# evpr.net
KiCad netlist of a schematic drawn in EAGLE
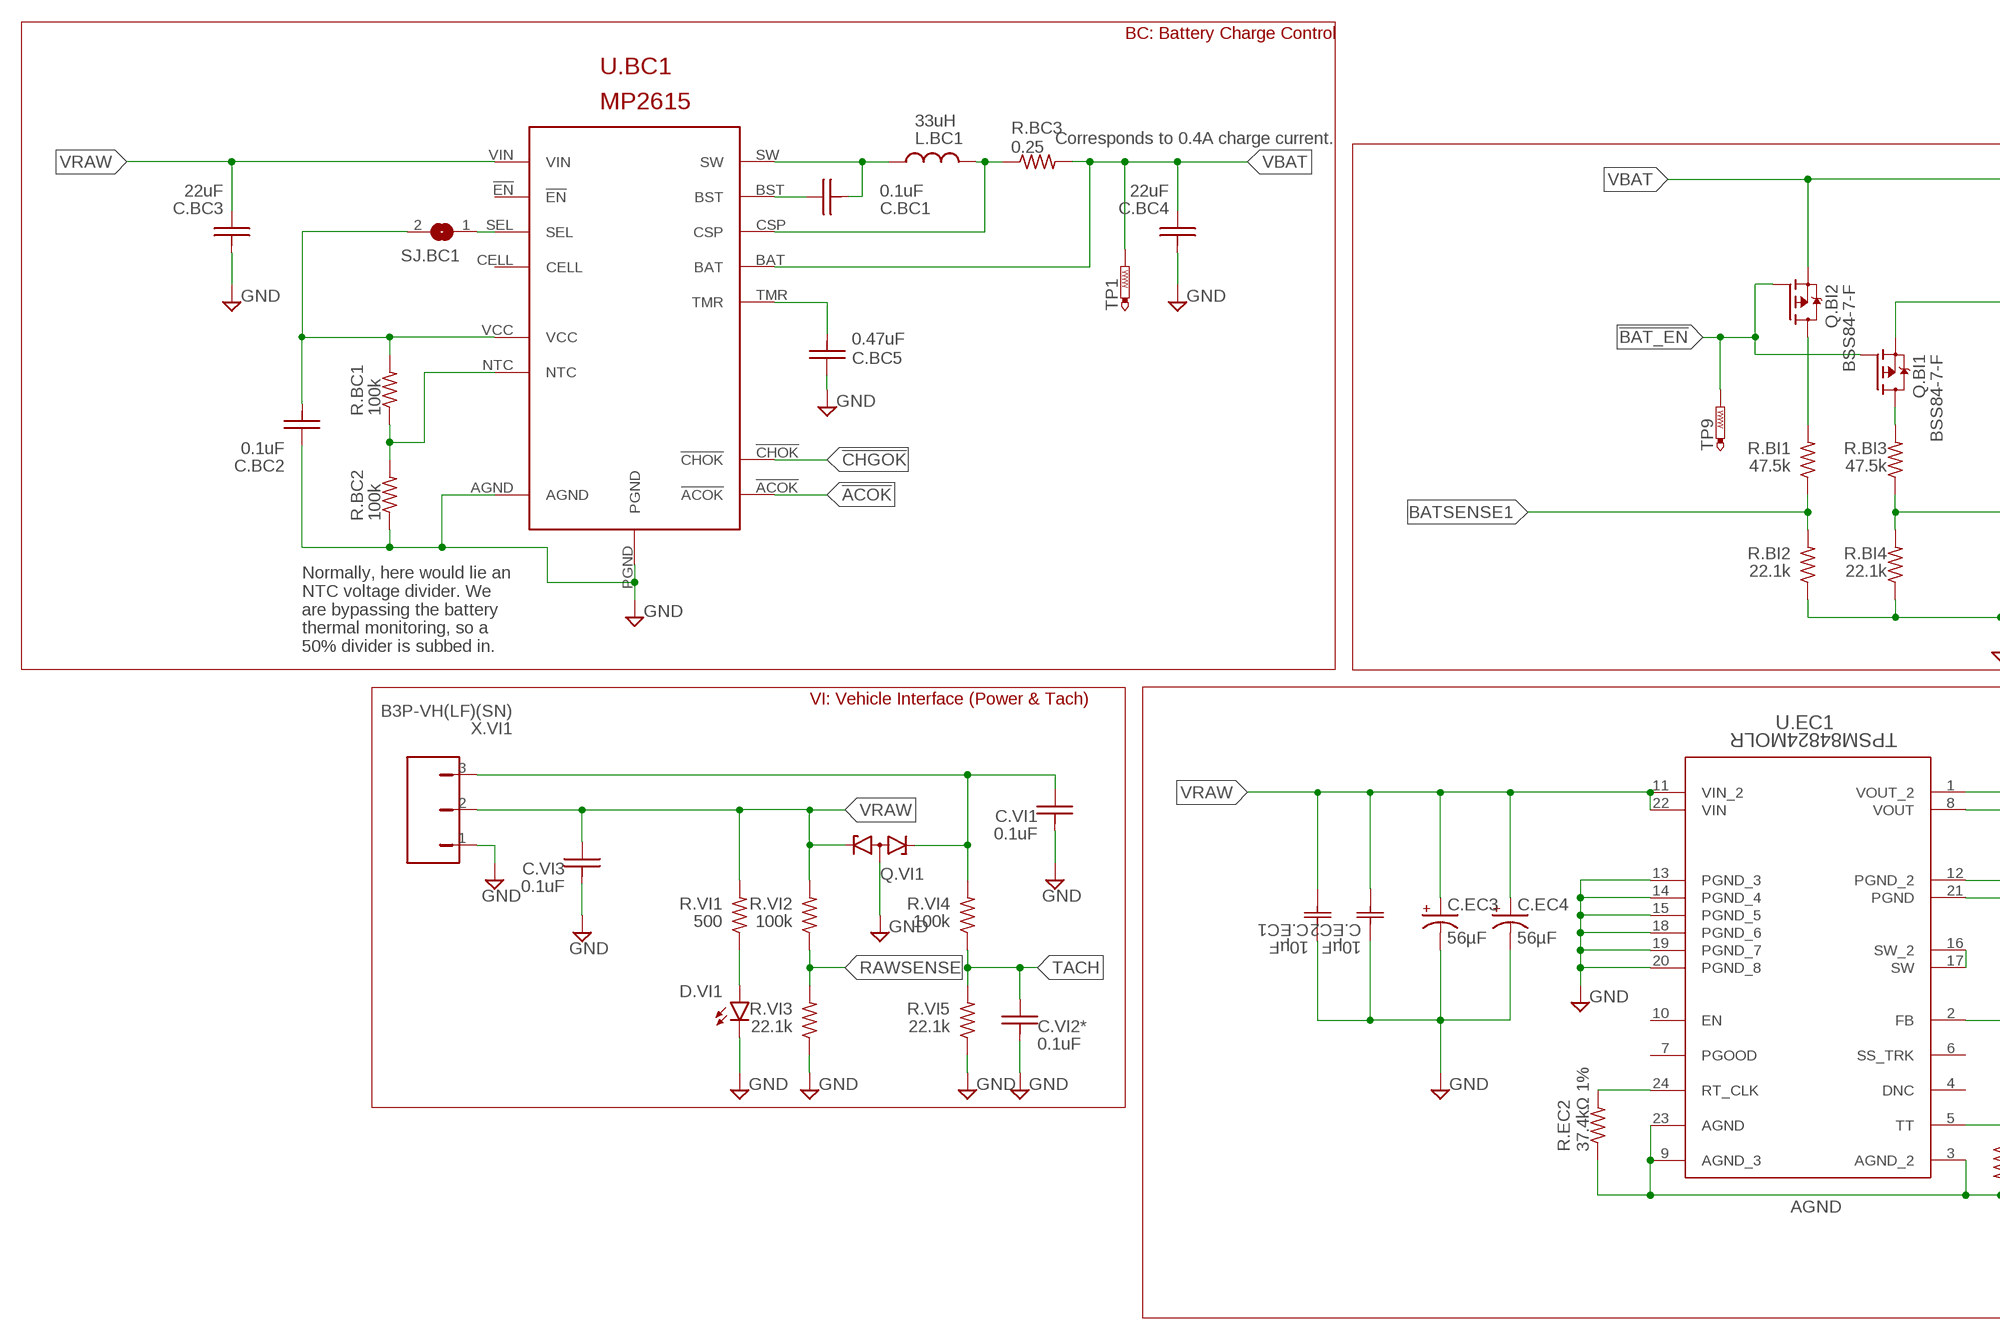
[diagram p0: schematic, sheet 1, part 1 of 2]
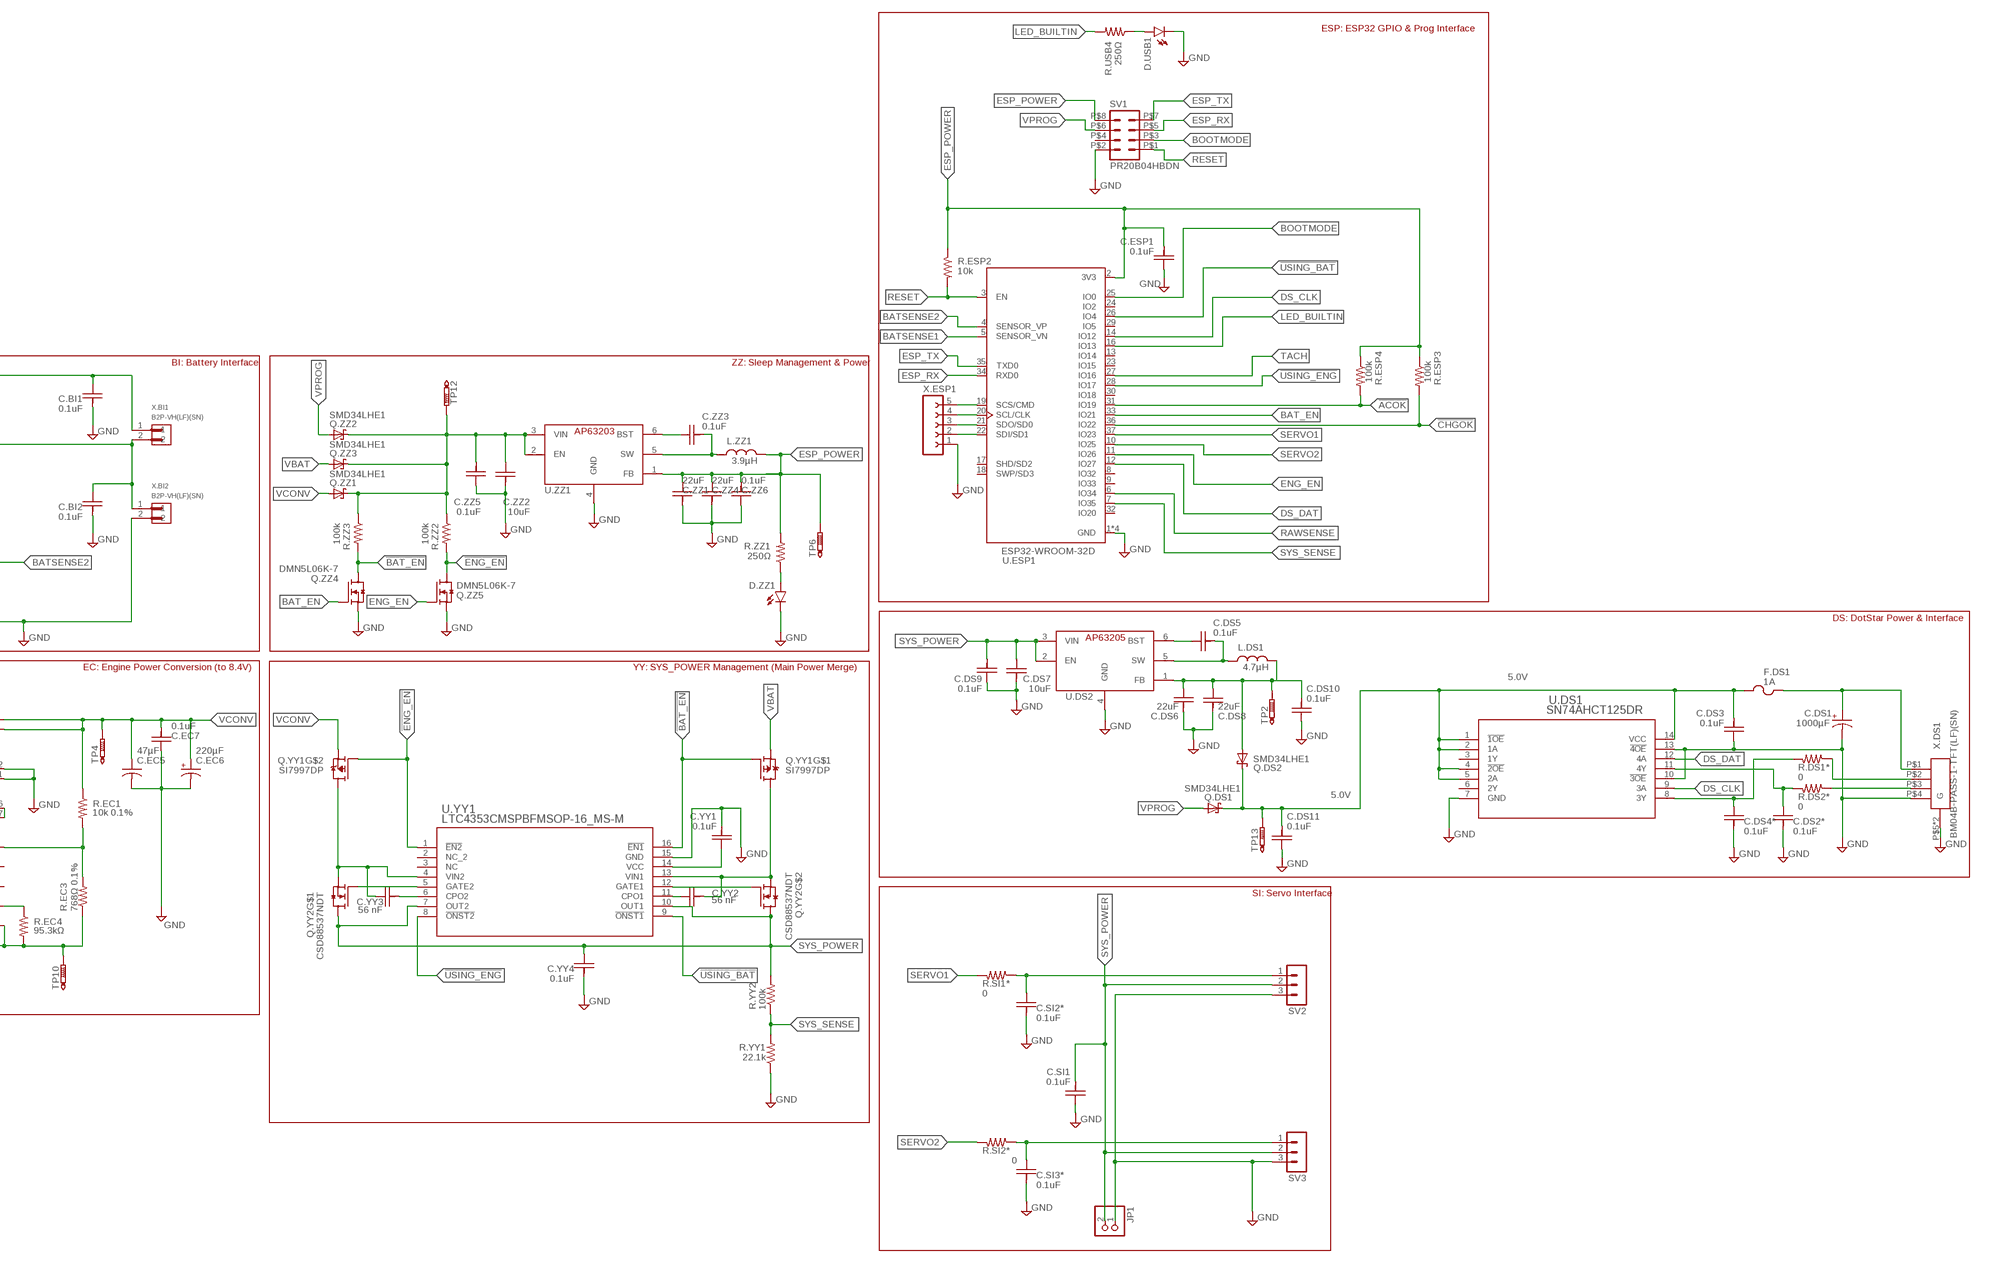
[diagram p1: schematic, sheet 1, part 2 of 2]

(export (version "E")
  (design (tool "Eeschema 10.0.6"))
  (components
    (comp (ref "C.BC1")
      (value "0.1uF")
      (footprint "eagle-import:C0603")
      (libsource (lib "eagle-import") (part "C0603"))
    )
    (comp (ref "C.BC2")
      (value "0.1uF")
      (footprint "eagle-import:C0603")
      (libsource (lib "eagle-import") (part "C0603"))
    )
    (comp (ref "C.BC3")
      (value "22uF")
      (footprint "eagle-import:C0603")
      (libsource (lib "eagle-import") (part "C0603"))
    )
    (comp (ref "C.BC4")
      (value "22uF")
      (footprint "eagle-import:C0603")
      (libsource (lib "eagle-import") (part "C0603"))
    )
    (comp (ref "C.BC5")
      (value "0.47uF")
      (footprint "eagle-import:C0603")
      (libsource (lib "eagle-import") (part "C0603"))
    )
    (comp (ref "C.BI1")
      (value "0.1uF")
      (footprint "eagle-import:C0603")
      (libsource (lib "eagle-import") (part "C0603"))
    )
    (comp (ref "C.BI2")
      (value "0.1uF")
      (footprint "eagle-import:C0603")
      (libsource (lib "eagle-import") (part "C0603"))
    )
    (comp (ref "C.DS1")
      (value "1000µF")
      (footprint "eagle-import:810RADCAN")
      (libsource (lib "eagle-import") (part "810RADCAP"))
    )
    (comp (ref "C.DS2*")
      (value "0.1uF")
      (footprint "eagle-import:C0603")
      (libsource (lib "eagle-import") (part "C0603"))
    )
    (comp (ref "C.DS3")
      (value "0.1uF")
      (footprint "eagle-import:C0603")
      (libsource (lib "eagle-import") (part "C0603"))
    )
    (comp (ref "C.DS4*")
      (value "0.1uF")
      (footprint "eagle-import:C0603")
      (libsource (lib "eagle-import") (part "C0603"))
    )
    (comp (ref "C.DS5")
      (value "0.1uF")
      (footprint "eagle-import:C0603")
      (libsource (lib "eagle-import") (part "C0603"))
    )
    (comp (ref "C.DS6")
      (value "22uF")
      (footprint "eagle-import:C0603")
      (libsource (lib "eagle-import") (part "C0603"))
    )
    (comp (ref "C.DS7")
      (value "10uF")
      (footprint "eagle-import:C0603")
      (libsource (lib "eagle-import") (part "C0603"))
    )
    (comp (ref "C.DS8")
      (value "22uF")
      (footprint "eagle-import:C0603")
      (libsource (lib "eagle-import") (part "C0603"))
    )
    (comp (ref "C.DS9")
      (value "0.1uF")
      (footprint "eagle-import:C0603")
      (libsource (lib "eagle-import") (part "C0603"))
    )
    (comp (ref "C.DS10")
      (value "0.1uF")
      (footprint "eagle-import:C0603")
      (libsource (lib "eagle-import") (part "C0603"))
    )
    (comp (ref "C.DS11")
      (value "0.1uF")
      (footprint "eagle-import:C0603")
      (libsource (lib "eagle-import") (part "C0603"))
    )
    (comp (ref "C.EC1")
      (value "10µF")
      (footprint "eagle-import:CAP_3225")
      (libsource (lib "eagle-import") (part "C3225X7R1E106K250AC"))
    )
    (comp (ref "C.EC2")
      (value "10µF")
      (footprint "eagle-import:CAP_3225")
      (libsource (lib "eagle-import") (part "C3225X7R1E106K250AC"))
    )
    (comp (ref "C.EC3")
      (value "56µF")
      (footprint "eagle-import:OSCON_SVPF_6.3MM")
      (libsource (lib "eagle-import") (part "6.3MMCAP"))
    )
    (comp (ref "C.EC4")
      (value "56µF")
      (footprint "eagle-import:OSCON_SVPF_6.3MM")
      (libsource (lib "eagle-import") (part "6.3MMCAP"))
    )
    (comp (ref "C.EC5")
      (value "47µF")
      (footprint "eagle-import:C1210")
      (libsource (lib "eagle-import") (part "C-USC1210"))
    )
    (comp (ref "C.EC6")
      (value "220µF")
      (footprint "eagle-import:C6CYLCAP")
      (libsource (lib "eagle-import") (part "WURTH875115352003"))
    )
    (comp (ref "C.EC7")
      (value "0.1uF")
      (footprint "eagle-import:C0603")
      (libsource (lib "eagle-import") (part "C0603"))
    )
    (comp (ref "C.ESP1")
      (value "0.1uF")
      (footprint "eagle-import:C0603")
      (libsource (lib "eagle-import") (part "C0603"))
    )
    (comp (ref "C.SI1")
      (value "0.1uF")
      (footprint "eagle-import:C0603")
      (libsource (lib "eagle-import") (part "C0603"))
    )
    (comp (ref "C.SI2*")
      (value "0.1uF")
      (footprint "eagle-import:C0603")
      (libsource (lib "eagle-import") (part "C0603"))
    )
    (comp (ref "C.SI3*")
      (value "0.1uF")
      (footprint "eagle-import:C0603")
      (libsource (lib "eagle-import") (part "C0603"))
    )
    (comp (ref "C.VI1")
      (value "0.1uF")
      (footprint "eagle-import:C0603")
      (libsource (lib "eagle-import") (part "C0603"))
    )
    (comp (ref "C.VI2*")
      (value "0.1uF")
      (footprint "eagle-import:C0603")
      (libsource (lib "eagle-import") (part "C0603"))
    )
    (comp (ref "C.VI3")
      (value "0.1uF")
      (footprint "eagle-import:C0603")
      (libsource (lib "eagle-import") (part "C0603"))
    )
    (comp (ref "C.YY1")
      (value "0.1uF")
      (footprint "eagle-import:C0603")
      (libsource (lib "eagle-import") (part "C0603"))
    )
    (comp (ref "C.YY2")
      (value "56 nF")
      (footprint "eagle-import:C0603")
      (libsource (lib "eagle-import") (part "C0603"))
    )
    (comp (ref "C.YY3")
      (value "56 nF")
      (footprint "eagle-import:C0603")
      (libsource (lib "eagle-import") (part "C0603"))
    )
    (comp (ref "C.YY4")
      (value "0.1uF")
      (footprint "eagle-import:C0603")
      (libsource (lib "eagle-import") (part "C0603"))
    )
    (comp (ref "C.ZZ1")
      (value "22uF")
      (footprint "eagle-import:C0603")
      (libsource (lib "eagle-import") (part "C0603"))
    )
    (comp (ref "C.ZZ2")
      (value "10uF")
      (footprint "eagle-import:C0603")
      (libsource (lib "eagle-import") (part "C0603"))
    )
    (comp (ref "C.ZZ3")
      (value "0.1uF")
      (footprint "eagle-import:C0603")
      (libsource (lib "eagle-import") (part "C0603"))
    )
    (comp (ref "C.ZZ4")
      (value "22uF")
      (footprint "eagle-import:C0603")
      (libsource (lib "eagle-import") (part "C0603"))
    )
    (comp (ref "C.ZZ5")
      (value "0.1uF")
      (footprint "eagle-import:C0603")
      (libsource (lib "eagle-import") (part "C0603"))
    )
    (comp (ref "C.ZZ6")
      (value "0.1uF")
      (footprint "eagle-import:C0603")
      (libsource (lib "eagle-import") (part "C0603"))
    )
    (comp (ref "D.USB1")
      (value "LEDCHIP-LED0805")
      (footprint "eagle-import:CHIP-LED0805")
      (libsource (lib "eagle-import") (part "LEDCHIP-LED0805"))
    )
    (comp (ref "D.VI1")
      (value "LEDCHIP-LED0805")
      (footprint "eagle-import:CHIP-LED0805")
      (libsource (lib "eagle-import") (part "LEDCHIP-LED0805"))
    )
    (comp (ref "D.ZZ1")
      (value "LEDCHIP-LED0805")
      (footprint "eagle-import:CHIP-LED0805")
      (libsource (lib "eagle-import") (part "LEDCHIP-LED0805"))
    )
    (comp (ref "F.DS1")
      (value "1A")
      (footprint "eagle-import:C1-M")
      (fields (field (name "MANUFACTURER_PART_NUMBER") "C1Q 1"))
      (libsource (lib "eagle-import") (part "C1Q_1C1-M"))
    )
    (comp (ref "JP1")
      (value "PINHD-1X2")
      (footprint "eagle-import:1X02")
      (libsource (lib "eagle-import") (part "PINHD-1X2"))
    )
    (comp (ref "L.BC1")
      (value "33uH")
      (footprint "eagle-import:SRN5040TA")
      (libsource (lib "eagle-import") (part "SRN5040TA-330M"))
    )
    (comp (ref "L.DS1")
      (value "4.7µH")
      (footprint "eagle-import:SRR4818A-XXXX")
      (libsource (lib "eagle-import") (part "SRR4818A-XXXX"))
    )
    (comp (ref "L.ZZ1")
      (value "3.9µH")
      (footprint "eagle-import:SRR4818A-XXXX")
      (libsource (lib "eagle-import") (part "SRR4818A-XXXX"))
    )
    (comp (ref "Q.BI1")
      (value "BSS84-7-F")
      (footprint "eagle-import:SOT23")
      (libsource (lib "eagle-import") (part "BSS84-7-F"))
    )
    (comp (ref "Q.BI2")
      (value "BSS84-7-F")
      (footprint "eagle-import:SOT23")
      (libsource (lib "eagle-import") (part "BSS84-7-F"))
    )
    (comp (ref "Q.DS1")
      (value "SMD34LHE1")
      (footprint "eagle-import:SOD-123HE1")
      (libsource (lib "eagle-import") (part "SMD34LHE1"))
    )
    (comp (ref "Q.DS2")
      (value "SMD34LHE1")
      (footprint "eagle-import:SOD-123HE1")
      (libsource (lib "eagle-import") (part "SMD34LHE1"))
    )
    (comp (ref "Q.VI1")
      (value "VESD16A2-03G-G3-08")
      (footprint "eagle-import:SOT23")
      (libsource (lib "eagle-import") (part "VESD16A2-03G-G3-08"))
    )
    (comp (ref "Q.YY1")
      (value "SI7997DP")
      (footprint "eagle-import:POWERPAK_SO8DUAL")
      (libsource (lib "eagle-import") (part "SI7997DP"))
    )
    (comp (ref "Q.YY2")
      (value "CSD88537NDT")
      (footprint "eagle-import:SOIC8")
      (fields (field (name "COMPONENT") "CSD88537NDT"))
      (libsource (lib "eagle-import") (part "CSD88537NDT"))
    )
    (comp (ref "Q.ZZ1")
      (value "SMD34LHE1")
      (footprint "eagle-import:SOD-123HE1")
      (libsource (lib "eagle-import") (part "SMD34LHE1"))
    )
    (comp (ref "Q.ZZ2")
      (value "SMD34LHE1")
      (footprint "eagle-import:SOD-123HE1")
      (libsource (lib "eagle-import") (part "SMD34LHE1"))
    )
    (comp (ref "Q.ZZ3")
      (value "SMD34LHE1")
      (footprint "eagle-import:SOD-123HE1")
      (libsource (lib "eagle-import") (part "SMD34LHE1"))
    )
    (comp (ref "Q.ZZ4")
      (value "DMN5L06K-7")
      (footprint "eagle-import:SOT23")
      (libsource (lib "eagle-import") (part "DMN5L06K-7"))
    )
    (comp (ref "Q.ZZ5")
      (value "DMN5L06K-7")
      (footprint "eagle-import:SOT23")
      (libsource (lib "eagle-import") (part "DMN5L06K-7"))
    )
    (comp (ref "R.BC1")
      (value "100k")
      (footprint "eagle-import:R0603")
      (libsource (lib "eagle-import") (part "R0603"))
    )
    (comp (ref "R.BC2")
      (value "100k")
      (footprint "eagle-import:R0603")
      (libsource (lib "eagle-import") (part "R0603"))
    )
    (comp (ref "R.BC3")
      (value "0.25")
      (footprint "eagle-import:R0603")
      (libsource (lib "eagle-import") (part "R0603"))
    )
    (comp (ref "R.BI1")
      (value "47.5k")
      (footprint "eagle-import:R0603")
      (libsource (lib "eagle-import") (part "R0603"))
    )
    (comp (ref "R.BI2")
      (value "22.1k")
      (footprint "eagle-import:R0603")
      (libsource (lib "eagle-import") (part "R0603"))
    )
    (comp (ref "R.BI3")
      (value "47.5k")
      (footprint "eagle-import:R0603")
      (libsource (lib "eagle-import") (part "R0603"))
    )
    (comp (ref "R.BI4")
      (value "22.1k")
      (footprint "eagle-import:R0603")
      (libsource (lib "eagle-import") (part "R0603"))
    )
    (comp (ref "R.DS1*")
      (value "0")
      (footprint "eagle-import:R0603")
      (libsource (lib "eagle-import") (part "R0603"))
    )
    (comp (ref "R.DS2*")
      (value "0")
      (footprint "eagle-import:R0603")
      (libsource (lib "eagle-import") (part "R0603"))
    )
    (comp (ref "R.EC1")
      (value "10k 0.1%")
      (footprint "eagle-import:R0603")
      (libsource (lib "eagle-import") (part "R0603"))
    )
    (comp (ref "R.EC2")
      (value "37.4kΩ 1%")
      (footprint "eagle-import:R0603")
      (libsource (lib "eagle-import") (part "R0603"))
    )
    (comp (ref "R.EC3")
      (value "768Ω 0.1%")
      (footprint "eagle-import:R0603")
      (libsource (lib "eagle-import") (part "R0603"))
    )
    (comp (ref "R.EC4")
      (value "95.3kΩ")
      (footprint "eagle-import:R0603")
      (libsource (lib "eagle-import") (part "R0603"))
    )
    (comp (ref "R.ESP2")
      (value "10k")
      (footprint "eagle-import:R0603")
      (libsource (lib "eagle-import") (part "R0603"))
    )
    (comp (ref "R.ESP3")
      (value "100k")
      (footprint "eagle-import:R0603")
      (libsource (lib "eagle-import") (part "R0603"))
    )
    (comp (ref "R.ESP4")
      (value "100k")
      (footprint "eagle-import:R0603")
      (libsource (lib "eagle-import") (part "R0603"))
    )
    (comp (ref "R.SI1*")
      (value "0")
      (footprint "eagle-import:R0603")
      (libsource (lib "eagle-import") (part "R0603"))
    )
    (comp (ref "R.SI2*")
      (value "0")
      (footprint "eagle-import:R0603")
      (libsource (lib "eagle-import") (part "R0603"))
    )
    (comp (ref "R.USB4")
      (value "250Ω")
      (footprint "eagle-import:R0603")
      (libsource (lib "eagle-import") (part "R0603"))
    )
    (comp (ref "R.VI1")
      (value "500")
      (footprint "eagle-import:R0603")
      (libsource (lib "eagle-import") (part "R0603"))
    )
    (comp (ref "R.VI2")
      (value "100k")
      (footprint "eagle-import:R0603")
      (libsource (lib "eagle-import") (part "R0603"))
    )
    (comp (ref "R.VI3")
      (value "22.1k")
      (footprint "eagle-import:R0603")
      (libsource (lib "eagle-import") (part "R0603"))
    )
    (comp (ref "R.VI4")
      (value "100k")
      (footprint "eagle-import:R0603")
      (libsource (lib "eagle-import") (part "R0603"))
    )
    (comp (ref "R.VI5")
      (value "22.1k")
      (footprint "eagle-import:R0603")
      (libsource (lib "eagle-import") (part "R0603"))
    )
    (comp (ref "R.YY1")
      (value "22.1k")
      (footprint "eagle-import:R0603")
      (libsource (lib "eagle-import") (part "R0603"))
    )
    (comp (ref "R.YY2")
      (value "100k")
      (footprint "eagle-import:R0603")
      (libsource (lib "eagle-import") (part "R0603"))
    )
    (comp (ref "R.ZZ1")
      (value "250Ω")
      (footprint "eagle-import:R0603")
      (libsource (lib "eagle-import") (part "R0603"))
    )
    (comp (ref "R.ZZ2")
      (value "100k")
      (footprint "eagle-import:R0603")
      (libsource (lib "eagle-import") (part "R0603"))
    )
    (comp (ref "R.ZZ3")
      (value "100k")
      (footprint "eagle-import:R0603")
      (libsource (lib "eagle-import") (part "R0603"))
    )
    (comp (ref "SJ.BC1")
      (value "SJ")
      (footprint "eagle-import:SJ")
      (libsource (lib "eagle-import") (part "SJ"))
    )
    (comp (ref "SV1")
      (value "PR20B04HBDN")
      (footprint "eagle-import:PR20B04HBDN")
      (libsource (lib "eagle-import") (part "PR20B04HBDN"))
    )
    (comp (ref "SV2")
      (value "MA03-1")
      (footprint "eagle-import:MA03-1")
      (libsource (lib "eagle-import") (part "MA03-1"))
    )
    (comp (ref "SV3")
      (value "MA03-1")
      (footprint "eagle-import:MA03-1")
      (libsource (lib "eagle-import") (part "MA03-1"))
    )
    (comp (ref "TP1")
      (value "PTR1TP10R")
      (footprint "eagle-import:TP10R")
      (libsource (lib "eagle-import") (part "PTR1TP10R"))
    )
    (comp (ref "TP2")
      (value "PTR1TP10R")
      (footprint "eagle-import:TP10R")
      (libsource (lib "eagle-import") (part "PTR1TP10R"))
    )
    (comp (ref "TP4")
      (value "PTR1TP10R")
      (footprint "eagle-import:TP10R")
      (libsource (lib "eagle-import") (part "PTR1TP10R"))
    )
    (comp (ref "TP6")
      (value "PTR1TP10R")
      (footprint "eagle-import:TP10R")
      (libsource (lib "eagle-import") (part "PTR1TP10R"))
    )
    (comp (ref "TP9")
      (value "PTR1TP10R")
      (footprint "eagle-import:TP10R")
      (libsource (lib "eagle-import") (part "PTR1TP10R"))
    )
    (comp (ref "TP10")
      (value "PTR1TP10R")
      (footprint "eagle-import:TP10R")
      (libsource (lib "eagle-import") (part "PTR1TP10R"))
    )
    (comp (ref "TP12")
      (value "PTR1TP10R")
      (footprint "eagle-import:TP10R")
      (libsource (lib "eagle-import") (part "PTR1TP10R"))
    )
    (comp (ref "TP13")
      (value "PTR1TP10R")
      (footprint "eagle-import:TP10R")
      (libsource (lib "eagle-import") (part "PTR1TP10R"))
    )
    (comp (ref "U.BC1")
      (value "MP2615")
      (footprint "eagle-import:QFN16")
      (libsource (lib "eagle-import") (part "MP2615"))
    )
    (comp (ref "U.DS1")
      (value "SN74AHCT125DR")
      (footprint "eagle-import:D14")
      (libsource (lib "eagle-import") (part "SN74AHCT125DR"))
    )
    (comp (ref "U.DS2")
      (value "AP63205")
      (footprint "eagle-import:TSOT23-6")
      (libsource (lib "eagle-import") (part "AP63205"))
    )
    (comp (ref "U.EC1")
      (value "TPSM84824MOLR")
      (footprint "eagle-import:MOL0024A")
      (libsource (lib "eagle-import") (part "TPSM84824MOLR"))
    )
    (comp (ref "U.ESP1")
      (value "ESP32-WROOM-32D")
      (footprint "eagle-import:MODULE_ESP32-WROOM-32D")
      (fields (field (name "MF") "Espressif Systems"))
      (libsource (lib "eagle-import") (part "ESP32-WROOM-32D"))
    )
    (comp (ref "U.YY1")
      (value "LTC4353CMSPBFMSOP-16_MS-M")
      (footprint "eagle-import:MSOP-16_MS-M")
      (fields (field (name "MANUFACTURER_PART_NUMBER") "LTC4353CMS#PBF"))
      (libsource (lib "eagle-import") (part "LTC4353CMSPBFMSOP-16_MS-M"))
    )
    (comp (ref "U.ZZ1")
      (value "AP63203")
      (footprint "eagle-import:TSOT23-6")
      (libsource (lib "eagle-import") (part "AP63203"))
    )
    (comp (ref "X.BI1")
      (value "B2P-VH(LF)(SN)")
      (footprint "eagle-import:JST_B2P-VH(LF)(SN)")
      (fields (field (name "MF") "JST Sales") (field (name "MP") "B2P-VH_LF__SN_"))
      (libsource (lib "eagle-import") (part "B2P-VH(LF)(SN)"))
    )
    (comp (ref "X.BI2")
      (value "B2P-VH(LF)(SN)")
      (footprint "eagle-import:JST_B2P-VH(LF)(SN)")
      (fields (field (name "MF") "JST Sales") (field (name "MP") "B2P-VH_LF__SN_"))
      (libsource (lib "eagle-import") (part "B2P-VH(LF)(SN)"))
    )
    (comp (ref "X.DS1")
      (value "BM04B-PASS-1-TFT(LF)(SN)")
      (footprint "eagle-import:BM04B-PASS-1-TFT(LF)(SN)")
      (libsource (lib "eagle-import") (part "BM04B-PASS-1-TFT(LF)(SN)"))
    )
    (comp (ref "X.ESP1")
      (value "FE05-1")
      (footprint "eagle-import:FE05-1")
      (libsource (lib "eagle-import") (part "FE05-1"))
    )
    (comp (ref "X.VI1")
      (value "B3P-VH(LF)(SN)")
      (footprint "eagle-import:B3P-VH")
      (fields (field (name "MF") "JST Sales") (field (name "MP") "B3P-VH_LF__SN_"))
      (libsource (lib "eagle-import") (part "B3P-VH(LF)(SN)"))
    )
  )
  (nets
    (net (code "1") (name "/5.0V") (class "Default")
      (node (ref "C.DS11") (pin "2") (pinfunction "2_2") (pintype "passive"))
      (node (ref "C.DS3") (pin "2") (pinfunction "2_2") (pintype "passive"))
      (node (ref "F.DS1") (pin "1") (pinfunction "1_1") (pintype "passive"))
      (node (ref "Q.DS1") (pin "C") (pinfunction "C_C") (pintype "passive"))
      (node (ref "Q.DS2") (pin "C") (pinfunction "C_C") (pintype "passive"))
      (node (ref "TP13") (pin "TP") (pinfunction "TP_TP") (pintype "input"))
      (node (ref "U.DS1") (pin "1") (pinfunction "~{1OE}_1") (pintype "input"))
      (node (ref "U.DS1") (pin "14") (pinfunction "VCC_14") (pintype "power_in"))
      (node (ref "U.DS1") (pin "2") (pinfunction "1A_2") (pintype "input"))
      (node (ref "U.DS1") (pin "4") (pinfunction "~{2OE}_4") (pintype "input"))
      (node (ref "U.DS1") (pin "5") (pinfunction "2A_5") (pintype "input"))
    )
    (net (code "2") (name "/AGND") (class "Default")
      (node (ref "R.EC2") (pin "1") (pinfunction "1_1") (pintype "passive"))
      (node (ref "R.EC3") (pin "1") (pinfunction "1_1") (pintype "passive"))
      (node (ref "R.EC4") (pin "2") (pinfunction "2_2") (pintype "passive"))
      (node (ref "TP10") (pin "TP") (pinfunction "TP_TP") (pintype "input"))
      (node (ref "U.EC1") (pin "23") (pinfunction "AGND_23") (pintype "power_in"))
      (node (ref "U.EC1") (pin "3") (pinfunction "AGND_2_3") (pintype "power_in"))
      (node (ref "U.EC1") (pin "9") (pinfunction "AGND_3_9") (pintype "power_in"))
    )
    (net (code "3") (name "/~{ACOK}") (class "Default")
      (node (ref "R.ESP4") (pin "2") (pinfunction "2_2") (pintype "passive"))
      (node (ref "U.BC1") (pin "!ACOK") (pinfunction "~{ACOK}_!ACOK") (pintype "bidirectional"))
      (node (ref "U.ESP1") (pin "31") (pinfunction "IO19_31") (pintype "bidirectional"))
    )
    (net (code "4") (name "/~{BAT_EN}") (class "Default")
      (node (ref "Q.BI1") (pin "1") (pinfunction "G_1") (pintype "passive"))
      (node (ref "Q.BI2") (pin "1") (pinfunction "G_1") (pintype "passive"))
      (node (ref "Q.YY1") (pin "P$2") (pinfunction "G_P$2") (pintype "passive"))
      (node (ref "Q.ZZ4") (pin "3") (pinfunction "D_3") (pintype "passive"))
      (node (ref "R.ZZ3") (pin "2") (pinfunction "2_2") (pintype "passive"))
      (node (ref "TP9") (pin "TP") (pinfunction "TP_TP") (pintype "input"))
      (node (ref "U.YY1") (pin "16") (pinfunction "~{EN1}_16") (pintype "input"))
    )
    (net (code "5") (name "/~{CHGOK}") (class "Default")
      (node (ref "R.ESP3") (pin "2") (pinfunction "2_2") (pintype "passive"))
      (node (ref "U.BC1") (pin "!CHOK") (pinfunction "~{CHOK}_!CHOK") (pintype "bidirectional"))
      (node (ref "U.ESP1") (pin "36") (pinfunction "IO22_36") (pintype "bidirectional"))
    )
    (net (code "6") (name "/~{ENG_EN}") (class "Default")
      (node (ref "Q.YY1") (pin "P$4") (pinfunction "G_P$4") (pintype "passive"))
      (node (ref "Q.ZZ5") (pin "3") (pinfunction "D_3") (pintype "passive"))
      (node (ref "R.ZZ2") (pin "2") (pinfunction "2_2") (pintype "passive"))
      (node (ref "U.YY1") (pin "1") (pinfunction "~{EN2}_1") (pintype "input"))
    )
    (net (code "7") (name "/~{USING_BAT}") (class "Default")
      (node (ref "U.ESP1") (pin "26") (pinfunction "IO4_26") (pintype "bidirectional"))
      (node (ref "U.YY1") (pin "9") (pinfunction "~{ONST1}_9") (pintype "output"))
    )
    (net (code "8") (name "/~{USING_ENG}") (class "Default")
      (node (ref "U.ESP1") (pin "28") (pinfunction "IO17_28") (pintype "bidirectional"))
      (node (ref "U.YY1") (pin "8") (pinfunction "~{ONST2}_8") (pintype "output"))
    )
    (net (code "9") (name "BATSENSE1") (class "Default")
      (node (ref "R.BI1") (pin "1") (pinfunction "1_1") (pintype "passive"))
      (node (ref "R.BI2") (pin "2") (pinfunction "2_2") (pintype "passive"))
      (node (ref "U.ESP1") (pin "5") (pinfunction "SENSOR_VN_5") (pintype "input"))
    )
    (net (code "10") (name "BATSENSE2") (class "Default")
      (node (ref "R.BI3") (pin "1") (pinfunction "1_1") (pintype "passive"))
      (node (ref "R.BI4") (pin "2") (pinfunction "2_2") (pintype "passive"))
      (node (ref "U.ESP1") (pin "4") (pinfunction "SENSOR_VP_4") (pintype "input"))
    )
    (net (code "11") (name "BAT_EN") (class "Default")
      (node (ref "Q.ZZ4") (pin "1") (pinfunction "G_1") (pintype "passive"))
      (node (ref "U.ESP1") (pin "33") (pinfunction "IO21_33") (pintype "bidirectional"))
    )
    (net (code "12") (name "BOOTMODE") (class "Default")
      (node (ref "SV1") (pin "P$3") (pinfunction "3_P$3") (pintype "passive"))
      (node (ref "U.ESP1") (pin "25") (pinfunction "IO0_25") (pintype "bidirectional"))
    )
    (net (code "13") (name "DS_CLK") (class "Default")
      (node (ref "U.DS1") (pin "9") (pinfunction "3A_9") (pintype "input"))
      (node (ref "U.ESP1") (pin "14") (pinfunction "IO12_14") (pintype "bidirectional"))
    )
    (net (code "14") (name "DS_DAT") (class "Default")
      (node (ref "U.DS1") (pin "12") (pinfunction "4A_12") (pintype "input"))
      (node (ref "U.ESP1") (pin "12") (pinfunction "IO27_12") (pintype "bidirectional"))
    )
    (net (code "15") (name "ENG_EN") (class "Default")
      (node (ref "Q.ZZ5") (pin "1") (pinfunction "G_1") (pintype "passive"))
      (node (ref "U.ESP1") (pin "11") (pinfunction "IO26_11") (pintype "bidirectional"))
    )
    (net (code "16") (name "ESP_POWER") (class "Default")
      (node (ref "C.ESP1") (pin "2") (pinfunction "2_2") (pintype "passive"))
      (node (ref "C.ZZ1") (pin "1") (pinfunction "1_1") (pintype "passive"))
      (node (ref "C.ZZ4") (pin "1") (pinfunction "1_1") (pintype "passive"))
      (node (ref "C.ZZ6") (pin "2") (pinfunction "2_2") (pintype "passive"))
      (node (ref "L.ZZ1") (pin "P$2") (pinfunction "2_P$2") (pintype "passive"))
      (node (ref "R.ESP2") (pin "1") (pinfunction "1_1") (pintype "passive"))
      (node (ref "R.ESP3") (pin "1") (pinfunction "1_1") (pintype "passive"))
      (node (ref "R.ESP4") (pin "1") (pinfunction "1_1") (pintype "passive"))
      (node (ref "R.ZZ1") (pin "2") (pinfunction "2_2") (pintype "passive"))
      (node (ref "SV1") (pin "P$8") (pinfunction "8_P$8") (pintype "passive"))
      (node (ref "TP6") (pin "TP") (pinfunction "TP_TP") (pintype "input"))
      (node (ref "U.ESP1") (pin "2") (pinfunction "3V3_2") (pintype "power_in"))
      (node (ref "U.ZZ1") (pin "1") (pinfunction "FB_1") (pintype "bidirectional"))
    )
    (net (code "17") (name "ESP_RX") (class "Default")
      (node (ref "SV1") (pin "P$5") (pinfunction "5_P$5") (pintype "passive"))
      (node (ref "U.ESP1") (pin "34") (pinfunction "RXD0_34") (pintype "bidirectional"))
    )
    (net (code "18") (name "ESP_TX") (class "Default")
      (node (ref "SV1") (pin "P$7") (pinfunction "7_P$7") (pintype "passive"))
      (node (ref "U.ESP1") (pin "35") (pinfunction "TXD0_35") (pintype "bidirectional"))
    )
    (net (code "19") (name "GND") (class "Default")
      (node (ref "C.BC2") (pin "1") (pinfunction "1_1") (pintype "passive"))
      (node (ref "C.BC3") (pin "2") (pinfunction "2_2") (pintype "passive"))
      (node (ref "C.BC4") (pin "2") (pinfunction "2_2") (pintype "passive"))
      (node (ref "C.BC5") (pin "1") (pinfunction "1_1") (pintype "passive"))
      (node (ref "C.BI1") (pin "2") (pinfunction "2_2") (pintype "passive"))
      (node (ref "C.BI2") (pin "2") (pinfunction "2_2") (pintype "passive"))
      (node (ref "C.DS1") (pin "C$2") (pinfunction "-_C$2") (pintype "passive"))
      (node (ref "C.DS10") (pin "1") (pinfunction "1_1") (pintype "passive"))
      (node (ref "C.DS11") (pin "1") (pinfunction "1_1") (pintype "passive"))
      (node (ref "C.DS2*") (pin "2") (pinfunction "2_2") (pintype "passive"))
      (node (ref "C.DS3") (pin "1") (pinfunction "1_1") (pintype "passive"))
      (node (ref "C.DS4*") (pin "2") (pinfunction "2_2") (pintype "passive"))
      (node (ref "C.DS6") (pin "2") (pinfunction "2_2") (pintype "passive"))
      (node (ref "C.DS7") (pin "2") (pinfunction "2_2") (pintype "passive"))
      (node (ref "C.DS8") (pin "2") (pinfunction "2_2") (pintype "passive"))
      (node (ref "C.DS9") (pin "1") (pinfunction "1_1") (pintype "passive"))
      (node (ref "C.EC1") (pin "1") (pinfunction "1_1") (pintype "passive"))
      (node (ref "C.EC2") (pin "1") (pinfunction "1_1") (pintype "passive"))
      (node (ref "C.EC3") (pin "-") (pinfunction "-_-") (pintype "passive"))
      (node (ref "C.EC4") (pin "-") (pinfunction "-_-") (pintype "passive"))
      (node (ref "C.EC5") (pin "2") (pinfunction "2_2") (pintype "passive"))
      (node (ref "C.EC6") (pin "P$1") (pinfunction "-_P$1") (pintype "passive"))
      (node (ref "C.EC7") (pin "1") (pinfunction "1_1") (pintype "passive"))
      (node (ref "C.ESP1") (pin "1") (pinfunction "1_1") (pintype "passive"))
      (node (ref "C.SI1") (pin "1") (pinfunction "1_1") (pintype "passive"))
      (node (ref "C.SI2*") (pin "2") (pinfunction "2_2") (pintype "passive"))
      (node (ref "C.SI3*") (pin "2") (pinfunction "2_2") (pintype "passive"))
      (node (ref "C.VI1") (pin "2") (pinfunction "2_2") (pintype "passive"))
      (node (ref "C.VI2*") (pin "2") (pinfunction "2_2") (pintype "passive"))
      (node (ref "C.VI3") (pin "2") (pinfunction "2_2") (pintype "passive"))
      (node (ref "C.YY1") (pin "2") (pinfunction "2_2") (pintype "passive"))
      (node (ref "C.YY4") (pin "2") (pinfunction "2_2") (pintype "passive"))
      (node (ref "C.ZZ1") (pin "2") (pinfunction "2_2") (pintype "passive"))
      (node (ref "C.ZZ2") (pin "2") (pinfunction "2_2") (pintype "passive"))
      (node (ref "C.ZZ4") (pin "2") (pinfunction "2_2") (pintype "passive"))
      (node (ref "C.ZZ5") (pin "1") (pinfunction "1_1") (pintype "passive"))
      (node (ref "C.ZZ6") (pin "1") (pinfunction "1_1") (pintype "passive"))
      (node (ref "D.USB1") (pin "C") (pinfunction "C_C") (pintype "passive"))
      (node (ref "D.VI1") (pin "C") (pinfunction "C_C") (pintype "passive"))
      (node (ref "D.ZZ1") (pin "C") (pinfunction "C_C") (pintype "passive"))
      (node (ref "JP1") (pin "1") (pinfunction "1_1") (pintype "passive"))
      (node (ref "Q.VI1") (pin "3") (pinfunction "AA_3") (pintype "passive"))
      (node (ref "Q.ZZ4") (pin "2") (pinfunction "S_2") (pintype "passive"))
      (node (ref "Q.ZZ5") (pin "2") (pinfunction "S_2") (pintype "passive"))
      (node (ref "R.BC2") (pin "1") (pinfunction "1_1") (pintype "passive"))
      (node (ref "R.BI2") (pin "1") (pinfunction "1_1") (pintype "passive"))
      (node (ref "R.BI4") (pin "1") (pinfunction "1_1") (pintype "passive"))
      (node (ref "R.VI3") (pin "1") (pinfunction "1_1") (pintype "passive"))
      (node (ref "R.VI5") (pin "1") (pinfunction "1_1") (pintype "passive"))
      (node (ref "R.YY1") (pin "1") (pinfunction "1_1") (pintype "passive"))
      (node (ref "SV1") (pin "P$2") (pinfunction "2_P$2") (pintype "passive"))
      (node (ref "SV2") (pin "3") (pinfunction "3_3") (pintype "passive"))
      (node (ref "SV3") (pin "3") (pinfunction "3_3") (pintype "passive"))
      (node (ref "U.BC1") (pin "AGND") (pinfunction "AGND_AGND") (pintype "bidirectional"))
      (node (ref "U.BC1") (pin "PGND") (pinfunction "PGND_PGND") (pintype "bidirectional"))
      (node (ref "U.DS1") (pin "10") (pinfunction "~{3OE}_10") (pintype "input"))
      (node (ref "U.DS1") (pin "13") (pinfunction "~{4OE}_13") (pintype "input"))
      (node (ref "U.DS1") (pin "7") (pinfunction "GND_7") (pintype "power_in"))
      (node (ref "U.DS2") (pin "4") (pinfunction "GND_4") (pintype "bidirectional"))
      (node (ref "U.EC1") (pin "12") (pinfunction "PGND_2_12") (pintype "power_in"))
      (node (ref "U.EC1") (pin "13") (pinfunction "PGND_3_13") (pintype "power_in"))
      (node (ref "U.EC1") (pin "14") (pinfunction "PGND_4_14") (pintype "power_in"))
      (node (ref "U.EC1") (pin "15") (pinfunction "PGND_5_15") (pintype "power_in"))
      (node (ref "U.EC1") (pin "18") (pinfunction "PGND_6_18") (pintype "power_in"))
      (node (ref "U.EC1") (pin "19") (pinfunction "PGND_7_19") (pintype "power_in"))
      (node (ref "U.EC1") (pin "20") (pinfunction "PGND_8_20") (pintype "power_in"))
      (node (ref "U.EC1") (pin "21") (pinfunction "PGND_21") (pintype "power_in"))
      (node (ref "U.ESP1") (pin "1") (pinfunction "GND_1") (pintype "power_in"))
      (node (ref "U.ESP1") (pin "15") (pinfunction "GND_15") (pintype "power_in"))
      (node (ref "U.ESP1") (pin "38") (pinfunction "GND_38") (pintype "power_in"))
      (node (ref "U.ESP1") (pin "39") (pinfunction "GND_39") (pintype "power_in"))
      (node (ref "U.YY1") (pin "15") (pinfunction "GND_15") (pintype "power_in"))
      (node (ref "U.ZZ1") (pin "4") (pinfunction "GND_4") (pintype "bidirectional"))
      (node (ref "X.BI2") (pin "2") (pinfunction "2_2") (pintype "passive"))
      (node (ref "X.DS1") (pin "P$4") (pinfunction "4_P$4") (pintype "passive"))
      (node (ref "X.DS1") (pin "P$5") (pinfunction "G_P$5") (pintype "passive"))
      (node (ref "X.DS1") (pin "P$6") (pinfunction "G_P$6") (pintype "passive"))
      (node (ref "X.ESP1") (pin "1") (pinfunction "1_1") (pintype "passive"))
      (node (ref "X.VI1") (pin "1") (pinfunction "1_1") (pintype "passive"))
    )
    (net (code "20") (name "LED_BUILTIN") (class "Default")
      (node (ref "R.USB4") (pin "2") (pinfunction "2_2") (pintype "passive"))
      (node (ref "U.ESP1") (pin "16") (pinfunction "IO13_16") (pintype "bidirectional"))
    )
    (net (code "21") (name "Net-(C.BC1-Pad1)") (class "Default")
      (node (ref "C.BC1") (pin "1") (pinfunction "1_1") (pintype "passive"))
      (node (ref "U.BC1") (pin "BST") (pinfunction "BST_BST") (pintype "bidirectional"))
    )
    (net (code "22") (name "Net-(C.BC2-Pad2)") (class "Default")
      (node (ref "C.BC2") (pin "2") (pinfunction "2_2") (pintype "passive"))
      (node (ref "R.BC1") (pin "2") (pinfunction "2_2") (pintype "passive"))
      (node (ref "SJ.BC1") (pin "2") (pinfunction "2_2") (pintype "passive"))
      (node (ref "U.BC1") (pin "VCC") (pinfunction "VCC_VCC") (pintype "bidirectional"))
    )
    (net (code "23") (name "Net-(C.BC5-Pad2)") (class "Default")
      (node (ref "C.BC5") (pin "2") (pinfunction "2_2") (pintype "passive"))
      (node (ref "U.BC1") (pin "TMR") (pinfunction "TMR_TMR") (pintype "bidirectional"))
    )
    (net (code "24") (name "Net-(C.DS1-+)") (class "Default")
      (node (ref "C.DS1") (pin "A$1") (pinfunction "+_A$1") (pintype "passive"))
      (node (ref "F.DS1") (pin "2") (pinfunction "2_2") (pintype "passive"))
      (node (ref "X.DS1") (pin "P$1") (pinfunction "1_P$1") (pintype "passive"))
    )
    (net (code "25") (name "Net-(C.SI2*-Pad1)") (class "Default")
      (node (ref "C.SI2*") (pin "1") (pinfunction "1_1") (pintype "passive"))
      (node (ref "R.SI1*") (pin "1") (pinfunction "1_1") (pintype "passive"))
      (node (ref "SV2") (pin "1") (pinfunction "1_1") (pintype "passive"))
    )
    (net (code "26") (name "Net-(C.SI3*-Pad1)") (class "Default")
      (node (ref "C.SI3*") (pin "1") (pinfunction "1_1") (pintype "passive"))
      (node (ref "R.SI2*") (pin "1") (pinfunction "1_1") (pintype "passive"))
      (node (ref "SV3") (pin "1") (pinfunction "1_1") (pintype "passive"))
    )
    (net (code "27") (name "Net-(D.USB1-PadA)") (class "Default")
      (node (ref "D.USB1") (pin "A") (pinfunction "A_A") (pintype "passive"))
      (node (ref "R.USB4") (pin "1") (pinfunction "1_1") (pintype "passive"))
    )
    (net (code "28") (name "Net-(D.VI1-PadA)") (class "Default")
      (node (ref "D.VI1") (pin "A") (pinfunction "A_A") (pintype "passive"))
      (node (ref "R.VI1") (pin "1") (pinfunction "1_1") (pintype "passive"))
    )
    (net (code "29") (name "Net-(D.ZZ1-PadA)") (class "Default")
      (node (ref "D.ZZ1") (pin "A") (pinfunction "A_A") (pintype "passive"))
      (node (ref "R.ZZ1") (pin "1") (pinfunction "1_1") (pintype "passive"))
    )
    (net (code "30") (name "Net-(L.BC1-1)") (class "Default")
      (node (ref "C.BC1") (pin "2") (pinfunction "2_2") (pintype "passive"))
      (node (ref "L.BC1") (pin "P$1") (pinfunction "1_P$1") (pintype "passive"))
      (node (ref "U.BC1") (pin "SW") (pinfunction "SW_SW") (pintype "bidirectional"))
    )
    (net (code "31") (name "Net-(L.BC1-2)") (class "Default")
      (node (ref "L.BC1") (pin "P$2") (pinfunction "2_P$2") (pintype "passive"))
      (node (ref "R.BC3") (pin "1") (pinfunction "1_1") (pintype "passive"))
      (node (ref "U.BC1") (pin "CSP") (pinfunction "CSP_CSP") (pintype "bidirectional"))
    )
    (net (code "32") (name "Net-(L.DS1-1)") (class "Default")
      (node (ref "C.DS5") (pin "2") (pinfunction "2_2") (pintype "passive"))
      (node (ref "L.DS1") (pin "P$1") (pinfunction "1_P$1") (pintype "passive"))
      (node (ref "U.DS2") (pin "5") (pinfunction "SW_5") (pintype "bidirectional"))
    )
    (net (code "33") (name "Net-(L.DS1-2)") (class "Default")
      (node (ref "C.DS10") (pin "2") (pinfunction "2_2") (pintype "passive"))
      (node (ref "C.DS6") (pin "1") (pinfunction "1_1") (pintype "passive"))
      (node (ref "C.DS8") (pin "1") (pinfunction "1_1") (pintype "passive"))
      (node (ref "L.DS1") (pin "P$2") (pinfunction "2_P$2") (pintype "passive"))
      (node (ref "Q.DS2") (pin "A") (pinfunction "A_A") (pintype "passive"))
      (node (ref "TP2") (pin "TP") (pinfunction "TP_TP") (pintype "input"))
      (node (ref "U.DS2") (pin "1") (pinfunction "FB_1") (pintype "bidirectional"))
    )
    (net (code "34") (name "Net-(L.ZZ1-1)") (class "Default")
      (node (ref "C.ZZ3") (pin "2") (pinfunction "2_2") (pintype "passive"))
      (node (ref "L.ZZ1") (pin "P$1") (pinfunction "1_P$1") (pintype "passive"))
      (node (ref "U.ZZ1") (pin "5") (pinfunction "SW_5") (pintype "bidirectional"))
    )
    (net (code "35") (name "Net-(Q.BI1-D)") (class "Default")
      (node (ref "Q.BI1") (pin "3") (pinfunction "D_3") (pintype "passive"))
      (node (ref "R.BI3") (pin "2") (pinfunction "2_2") (pintype "passive"))
    )
    (net (code "36") (name "Net-(Q.BI1-S)") (class "Default")
      (node (ref "C.BI2") (pin "1") (pinfunction "1_1") (pintype "passive"))
      (node (ref "Q.BI1") (pin "2") (pinfunction "S_2") (pintype "passive"))
      (node (ref "X.BI1") (pin "2") (pinfunction "2_2") (pintype "passive"))
      (node (ref "X.BI2") (pin "1") (pinfunction "1_1") (pintype "passive"))
    )
    (net (code "37") (name "Net-(Q.BI2-D)") (class "Default")
      (node (ref "Q.BI2") (pin "3") (pinfunction "D_3") (pintype "passive"))
      (node (ref "R.BI1") (pin "2") (pinfunction "2_2") (pintype "passive"))
    )
    (net (code "38") (name "Net-(Q.VI1-K1)") (class "Default")
      (node (ref "C.VI1") (pin "1") (pinfunction "1_1") (pintype "passive"))
      (node (ref "Q.VI1") (pin "2") (pinfunction "K1_2") (pintype "passive"))
      (node (ref "R.VI4") (pin "2") (pinfunction "2_2") (pintype "passive"))
      (node (ref "X.VI1") (pin "3") (pinfunction "3_3") (pintype "passive"))
    )
    (net (code "39") (name "Net-(Q.YY1A-D)") (class "Default")
      (node (ref "C.YY2") (pin "2") (pinfunction "2_2") (pintype "passive"))
      (node (ref "Q.YY1") (pin "D$1B") (pinfunction "D_D$1B") (pintype "passive"))
      (node (ref "Q.YY2") (pin "3") (pinfunction "S_3") (pintype "passive"))
      (node (ref "U.YY1") (pin "13") (pinfunction "VIN1_13") (pintype "input"))
    )
    (net (code "40") (name "Net-(Q.YY1B-D)") (class "Default")
      (node (ref "C.YY3") (pin "1") (pinfunction "1_1") (pintype "passive"))
      (node (ref "Q.YY1") (pin "D$2A") (pinfunction "D_D$2A") (pintype "passive"))
      (node (ref "Q.YY2") (pin "1") (pinfunction "S_1") (pintype "passive"))
      (node (ref "U.YY1") (pin "4") (pinfunction "VIN2_4") (pintype "input"))
    )
    (net (code "41") (name "Net-(Q.YY2A-G)") (class "Default")
      (node (ref "Q.YY2") (pin "2") (pinfunction "G_2") (pintype "passive"))
      (node (ref "U.YY1") (pin "5") (pinfunction "GATE2_5") (pintype "output"))
    )
    (net (code "42") (name "Net-(Q.YY2B-G)") (class "Default")
      (node (ref "Q.YY2") (pin "4") (pinfunction "G_4") (pintype "passive"))
      (node (ref "U.YY1") (pin "12") (pinfunction "GATE1_12") (pintype "output"))
    )
    (net (code "43") (name "Net-(R.BC1-Pad1)") (class "Default")
      (node (ref "R.BC1") (pin "1") (pinfunction "1_1") (pintype "passive"))
      (node (ref "R.BC2") (pin "2") (pinfunction "2_2") (pintype "passive"))
      (node (ref "U.BC1") (pin "NTC") (pinfunction "NTC_NTC") (pintype "bidirectional"))
    )
    (net (code "44") (name "Net-(SJ.BC1-Pad1)") (class "Default")
      (node (ref "SJ.BC1") (pin "1") (pinfunction "1_1") (pintype "passive"))
      (node (ref "U.BC1") (pin "SEL") (pinfunction "SEL_SEL") (pintype "bidirectional"))
    )
    (net (code "45") (name "Net-(U.DS1-3Y)") (class "Default")
      (node (ref "C.DS4*") (pin "1") (pinfunction "1_1") (pintype "passive"))
      (node (ref "R.DS1*") (pin "2") (pinfunction "2_2") (pintype "passive"))
      (node (ref "U.DS1") (pin "8") (pinfunction "3Y_8") (pintype "passive"))
    )
    (net (code "46") (name "Net-(U.DS1-4Y)") (class "Default")
      (node (ref "C.DS2*") (pin "1") (pinfunction "1_1") (pintype "passive"))
      (node (ref "R.DS2*") (pin "2") (pinfunction "2_2") (pintype "passive"))
      (node (ref "U.DS1") (pin "11") (pinfunction "4Y_11") (pintype "passive"))
    )
    (net (code "47") (name "Net-(U.DS2-BST)") (class "Default")
      (node (ref "C.DS5") (pin "1") (pinfunction "1_1") (pintype "passive"))
      (node (ref "U.DS2") (pin "6") (pinfunction "BST_6") (pintype "bidirectional"))
    )
    (net (code "48") (name "Net-(U.EC1-FB)") (class "Default")
      (node (ref "R.EC1") (pin "2") (pinfunction "2_2") (pintype "passive"))
      (node (ref "R.EC3") (pin "2") (pinfunction "2_2") (pintype "passive"))
      (node (ref "U.EC1") (pin "2") (pinfunction "FB_2") (pintype "input"))
    )
    (net (code "49") (name "Net-(U.EC1-RT_CLK)") (class "Default")
      (node (ref "R.EC2") (pin "2") (pinfunction "2_2") (pintype "passive"))
      (node (ref "U.EC1") (pin "24") (pinfunction "RT_CLK_24") (pintype "input"))
    )
    (net (code "50") (name "Net-(U.EC1-SW)") (class "Default")
      (node (ref "U.EC1") (pin "16") (pinfunction "SW_2_16") (pintype "output"))
      (node (ref "U.EC1") (pin "17") (pinfunction "SW_17") (pintype "output"))
    )
    (net (code "51") (name "Net-(U.EC1-TT)") (class "Default")
      (node (ref "R.EC4") (pin "1") (pinfunction "1_1") (pintype "passive"))
      (node (ref "U.EC1") (pin "5") (pinfunction "TT_5") (pintype "passive"))
    )
    (net (code "52") (name "Net-(U.ESP1-SCL{slash}CLK)") (class "Default")
      (node (ref "U.ESP1") (pin "20") (pinfunction "SCL/CLK_20") (pintype "bidirectional"))
      (node (ref "X.ESP1") (pin "4") (pinfunction "4_4") (pintype "passive"))
    )
    (net (code "53") (name "Net-(U.ESP1-SCS{slash}CMD)") (class "Default")
      (node (ref "U.ESP1") (pin "19") (pinfunction "SCS/CMD_19") (pintype "bidirectional"))
      (node (ref "X.ESP1") (pin "5") (pinfunction "5_5") (pintype "passive"))
    )
    (net (code "54") (name "Net-(U.ESP1-SDI{slash}SD1)") (class "Default")
      (node (ref "U.ESP1") (pin "22") (pinfunction "SDI/SD1_22") (pintype "bidirectional"))
      (node (ref "X.ESP1") (pin "2") (pinfunction "2_2") (pintype "passive"))
    )
    (net (code "55") (name "Net-(U.ESP1-SDO{slash}SD0)") (class "Default")
      (node (ref "U.ESP1") (pin "21") (pinfunction "SDO/SD0_21") (pintype "bidirectional"))
      (node (ref "X.ESP1") (pin "3") (pinfunction "3_3") (pintype "passive"))
    )
    (net (code "56") (name "Net-(U.YY1-CPO1)") (class "Default")
      (node (ref "C.YY2") (pin "1") (pinfunction "1_1") (pintype "passive"))
      (node (ref "U.YY1") (pin "11") (pinfunction "CPO1_11") (pintype "output"))
    )
    (net (code "57") (name "Net-(U.YY1-CPO2)") (class "Default")
      (node (ref "C.YY3") (pin "2") (pinfunction "2_2") (pintype "passive"))
      (node (ref "U.YY1") (pin "6") (pinfunction "CPO2_6") (pintype "output"))
    )
    (net (code "58") (name "Net-(U.YY1-VCC)") (class "Default")
      (node (ref "C.YY1") (pin "1") (pinfunction "1_1") (pintype "passive"))
      (node (ref "U.YY1") (pin "14") (pinfunction "VCC_14") (pintype "power_in"))
    )
    (net (code "59") (name "Net-(U.ZZ1-BST)") (class "Default")
      (node (ref "C.ZZ3") (pin "1") (pinfunction "1_1") (pintype "passive"))
      (node (ref "U.ZZ1") (pin "6") (pinfunction "BST_6") (pintype "bidirectional"))
    )
    (net (code "60") (name "Net-(U.ZZ1-EN)") (class "Default")
      (node (ref "C.ZZ2") (pin "1") (pinfunction "1_1") (pintype "passive"))
      (node (ref "C.ZZ5") (pin "2") (pinfunction "2_2") (pintype "passive"))
      (node (ref "Q.ZZ1") (pin "C") (pinfunction "C_C") (pintype "passive"))
      (node (ref "Q.ZZ2") (pin "C") (pinfunction "C_C") (pintype "passive"))
      (node (ref "Q.ZZ3") (pin "C") (pinfunction "C_C") (pintype "passive"))
      (node (ref "R.ZZ2") (pin "1") (pinfunction "1_1") (pintype "passive"))
      (node (ref "R.ZZ3") (pin "1") (pinfunction "1_1") (pintype "passive"))
      (node (ref "TP12") (pin "TP") (pinfunction "TP_TP") (pintype "input"))
      (node (ref "U.ZZ1") (pin "2") (pinfunction "EN_2") (pintype "bidirectional"))
      (node (ref "U.ZZ1") (pin "3") (pinfunction "VIN_3") (pintype "bidirectional"))
    )
    (net (code "61") (name "Net-(X.DS1-2)") (class "Default")
      (node (ref "R.DS1*") (pin "1") (pinfunction "1_1") (pintype "passive"))
      (node (ref "X.DS1") (pin "P$2") (pinfunction "2_P$2") (pintype "passive"))
    )
    (net (code "62") (name "Net-(X.DS1-3)") (class "Default")
      (node (ref "R.DS2*") (pin "1") (pinfunction "1_1") (pintype "passive"))
      (node (ref "X.DS1") (pin "P$3") (pinfunction "3_P$3") (pintype "passive"))
    )
    (net (code "63") (name "RAWSENSE") (class "Default")
      (node (ref "R.VI2") (pin "1") (pinfunction "1_1") (pintype "passive"))
      (node (ref "R.VI3") (pin "2") (pinfunction "2_2") (pintype "passive"))
      (node (ref "U.ESP1") (pin "6") (pinfunction "IO34_6") (pintype "bidirectional"))
    )
    (net (code "64") (name "RESET") (class "Default")
      (node (ref "R.ESP2") (pin "2") (pinfunction "2_2") (pintype "passive"))
      (node (ref "SV1") (pin "P$1") (pinfunction "1_P$1") (pintype "passive"))
      (node (ref "U.ESP1") (pin "3") (pinfunction "EN_3") (pintype "input"))
    )
    (net (code "65") (name "SERVO1") (class "Default")
      (node (ref "R.SI1*") (pin "2") (pinfunction "2_2") (pintype "passive"))
      (node (ref "U.ESP1") (pin "37") (pinfunction "IO23_37") (pintype "bidirectional"))
    )
    (net (code "66") (name "SERVO2") (class "Default")
      (node (ref "R.SI2*") (pin "2") (pinfunction "2_2") (pintype "passive"))
      (node (ref "U.ESP1") (pin "10") (pinfunction "IO25_10") (pintype "bidirectional"))
    )
    (net (code "67") (name "SYS_POWER") (class "Default")
      (node (ref "C.DS7") (pin "1") (pinfunction "1_1") (pintype "passive"))
      (node (ref "C.DS9") (pin "2") (pinfunction "2_2") (pintype "passive"))
      (node (ref "C.SI1") (pin "2") (pinfunction "2_2") (pintype "passive"))
      (node (ref "C.YY4") (pin "1") (pinfunction "1_1") (pintype "passive"))
      (node (ref "JP1") (pin "2") (pinfunction "2_2") (pintype "passive"))
      (node (ref "Q.YY2") (pin "5") (pinfunction "D_5") (pintype "passive"))
      (node (ref "Q.YY2") (pin "6") (pinfunction "D_6") (pintype "passive"))
      (node (ref "Q.YY2") (pin "7") (pinfunction "D_7") (pintype "passive"))
      (node (ref "Q.YY2") (pin "8") (pinfunction "D_8") (pintype "passive"))
      (node (ref "R.YY2") (pin "2") (pinfunction "2_2") (pintype "passive"))
      (node (ref "SV2") (pin "2") (pinfunction "2_2") (pintype "passive"))
      (node (ref "SV3") (pin "2") (pinfunction "2_2") (pintype "passive"))
      (node (ref "U.DS2") (pin "2") (pinfunction "EN_2") (pintype "bidirectional"))
      (node (ref "U.DS2") (pin "3") (pinfunction "VIN_3") (pintype "bidirectional"))
      (node (ref "U.YY1") (pin "10") (pinfunction "OUT1_10") (pintype "output"))
      (node (ref "U.YY1") (pin "7") (pinfunction "OUT2_7") (pintype "output"))
    )
    (net (code "68") (name "SYS_SENSE") (class "Default")
      (node (ref "R.YY1") (pin "2") (pinfunction "2_2") (pintype "passive"))
      (node (ref "R.YY2") (pin "1") (pinfunction "1_1") (pintype "passive"))
      (node (ref "U.ESP1") (pin "7") (pinfunction "IO35_7") (pintype "bidirectional"))
    )
    (net (code "69") (name "TACH") (class "Default")
      (node (ref "C.VI2*") (pin "1") (pinfunction "1_1") (pintype "passive"))
      (node (ref "R.VI4") (pin "1") (pinfunction "1_1") (pintype "passive"))
      (node (ref "R.VI5") (pin "2") (pinfunction "2_2") (pintype "passive"))
      (node (ref "U.ESP1") (pin "27") (pinfunction "IO16_27") (pintype "bidirectional"))
    )
    (net (code "70") (name "VBAT") (class "Default")
      (node (ref "C.BC4") (pin "1") (pinfunction "1_1") (pintype "passive"))
      (node (ref "C.BI1") (pin "1") (pinfunction "1_1") (pintype "passive"))
      (node (ref "Q.BI2") (pin "2") (pinfunction "S_2") (pintype "passive"))
      (node (ref "Q.YY1") (pin "P$1") (pinfunction "S_P$1") (pintype "passive"))
      (node (ref "Q.ZZ3") (pin "A") (pinfunction "A_A") (pintype "passive"))
      (node (ref "R.BC3") (pin "2") (pinfunction "2_2") (pintype "passive"))
      (node (ref "TP1") (pin "TP") (pinfunction "TP_TP") (pintype "input"))
      (node (ref "U.BC1") (pin "BAT") (pinfunction "BAT_BAT") (pintype "bidirectional"))
      (node (ref "X.BI1") (pin "1") (pinfunction "1_1") (pintype "passive"))
    )
    (net (code "71") (name "VCONV") (class "Default")
      (node (ref "C.EC5") (pin "1") (pinfunction "1_1") (pintype "passive"))
      (node (ref "C.EC6") (pin "P$2") (pinfunction "+_P$2") (pintype "passive"))
      (node (ref "C.EC7") (pin "2") (pinfunction "2_2") (pintype "passive"))
      (node (ref "Q.YY1") (pin "P$3") (pinfunction "S_P$3") (pintype "passive"))
      (node (ref "Q.ZZ1") (pin "A") (pinfunction "A_A") (pintype "passive"))
      (node (ref "R.EC1") (pin "1") (pinfunction "1_1") (pintype "passive"))
      (node (ref "TP4") (pin "TP") (pinfunction "TP_TP") (pintype "input"))
      (node (ref "U.EC1") (pin "1") (pinfunction "VOUT_2_1") (pintype "power_in"))
      (node (ref "U.EC1") (pin "8") (pinfunction "VOUT_8") (pintype "power_in"))
    )
    (net (code "72") (name "VPROG") (class "Default")
      (node (ref "Q.DS1") (pin "A") (pinfunction "A_A") (pintype "passive"))
      (node (ref "Q.ZZ2") (pin "A") (pinfunction "A_A") (pintype "passive"))
      (node (ref "SV1") (pin "P$6") (pinfunction "6_P$6") (pintype "passive"))
    )
    (net (code "73") (name "VRAW") (class "Default")
      (node (ref "C.BC3") (pin "1") (pinfunction "1_1") (pintype "passive"))
      (node (ref "C.EC1") (pin "2") (pinfunction "2_2") (pintype "passive"))
      (node (ref "C.EC2") (pin "2") (pinfunction "2_2") (pintype "passive"))
      (node (ref "C.EC3") (pin "+") (pinfunction "+_+") (pintype "passive"))
      (node (ref "C.EC4") (pin "+") (pinfunction "+_+") (pintype "passive"))
      (node (ref "C.VI3") (pin "1") (pinfunction "1_1") (pintype "passive"))
      (node (ref "Q.VI1") (pin "1") (pinfunction "K2_1") (pintype "passive"))
      (node (ref "R.VI1") (pin "2") (pinfunction "2_2") (pintype "passive"))
      (node (ref "R.VI2") (pin "2") (pinfunction "2_2") (pintype "passive"))
      (node (ref "U.BC1") (pin "VIN") (pinfunction "VIN_VIN") (pintype "bidirectional"))
      (node (ref "U.EC1") (pin "11") (pinfunction "VIN_2_11") (pintype "power_in"))
      (node (ref "U.EC1") (pin "22") (pinfunction "VIN_22") (pintype "power_in"))
      (node (ref "X.VI1") (pin "2") (pinfunction "2_2") (pintype "passive"))
    )
    (net (code "74") (name "unconnected-(SV1-4-PadP$4)") (class "Default")
      (node (ref "SV1") (pin "P$4") (pinfunction "4_P$4") (pintype "passive"))
    )
    (net (code "75") (name "unconnected-(U.BC1-PadCELL)") (class "Default")
      (node (ref "U.BC1") (pin "CELL") (pinfunction "CELL_CELL") (pintype "bidirectional"))
    )
    (net (code "76") (name "unconnected-(U.BC1-~{EN}-Pad!EN)") (class "Default")
      (node (ref "U.BC1") (pin "!EN") (pinfunction "~{EN}_!EN") (pintype "bidirectional"))
    )
    (net (code "77") (name "unconnected-(U.DS1-1Y-Pad3)") (class "Default")
      (node (ref "U.DS1") (pin "3") (pinfunction "1Y_3") (pintype "passive"))
    )
    (net (code "78") (name "unconnected-(U.DS1-2Y-Pad6)") (class "Default")
      (node (ref "U.DS1") (pin "6") (pinfunction "2Y_6") (pintype "passive"))
    )
    (net (code "79") (name "unconnected-(U.EC1-DNC-Pad4)") (class "Default")
      (node (ref "U.EC1") (pin "4") (pinfunction "DNC_4") (pintype "passive"))
    )
    (net (code "80") (name "unconnected-(U.EC1-EN-Pad10)") (class "Default")
      (node (ref "U.EC1") (pin "10") (pinfunction "EN_10") (pintype "input"))
    )
    (net (code "81") (name "unconnected-(U.EC1-PGOOD-Pad7)") (class "Default")
      (node (ref "U.EC1") (pin "7") (pinfunction "PGOOD_7") (pintype "passive"))
    )
    (net (code "82") (name "unconnected-(U.EC1-SS_TRK-Pad6)") (class "Default")
      (node (ref "U.EC1") (pin "6") (pinfunction "SS_TRK_6") (pintype "passive"))
    )
    (net (code "83") (name "unconnected-(U.ESP1-IO2-Pad24)") (class "Default")
      (node (ref "U.ESP1") (pin "24") (pinfunction "IO2_24") (pintype "bidirectional"))
    )
    (net (code "84") (name "unconnected-(U.ESP1-IO5-Pad29)") (class "Default")
      (node (ref "U.ESP1") (pin "29") (pinfunction "IO5_29") (pintype "bidirectional"))
    )
    (net (code "85") (name "unconnected-(U.ESP1-IO14-Pad13)") (class "Default")
      (node (ref "U.ESP1") (pin "13") (pinfunction "IO14_13") (pintype "bidirectional"))
    )
    (net (code "86") (name "unconnected-(U.ESP1-IO15-Pad23)") (class "Default")
      (node (ref "U.ESP1") (pin "23") (pinfunction "IO15_23") (pintype "bidirectional"))
    )
    (net (code "87") (name "unconnected-(U.ESP1-IO18-Pad30)") (class "Default")
      (node (ref "U.ESP1") (pin "30") (pinfunction "IO18_30") (pintype "bidirectional"))
    )
    (net (code "88") (name "unconnected-(U.ESP1-IO20-Pad32)") (class "Default")
      (node (ref "U.ESP1") (pin "32") (pinfunction "IO20_32") (pintype "bidirectional"))
    )
    (net (code "89") (name "unconnected-(U.ESP1-IO32-Pad8)") (class "Default")
      (node (ref "U.ESP1") (pin "8") (pinfunction "IO32_8") (pintype "bidirectional"))
    )
    (net (code "90") (name "unconnected-(U.ESP1-IO33-Pad9)") (class "Default")
      (node (ref "U.ESP1") (pin "9") (pinfunction "IO33_9") (pintype "bidirectional"))
    )
    (net (code "91") (name "unconnected-(U.ESP1-SHD{slash}SD2-Pad17)") (class "Default")
      (node (ref "U.ESP1") (pin "17") (pinfunction "SHD/SD2_17") (pintype "bidirectional"))
    )
    (net (code "92") (name "unconnected-(U.ESP1-SWP{slash}SD3-Pad18)") (class "Default")
      (node (ref "U.ESP1") (pin "18") (pinfunction "SWP/SD3_18") (pintype "bidirectional"))
    )
    (net (code "93") (name "unconnected-(U.YY1-NC-Pad3)") (class "Default")
      (node (ref "U.YY1") (pin "3") (pinfunction "NC_3") (pintype "no_connect"))
    )
    (net (code "94") (name "unconnected-(U.YY1-NC_2-Pad2)") (class "Default")
      (node (ref "U.YY1") (pin "2") (pinfunction "NC_2_2") (pintype "no_connect"))
    )
  )
)
